# BeamBreak.net
KiCad netlist of a schematic drawn in EAGLE
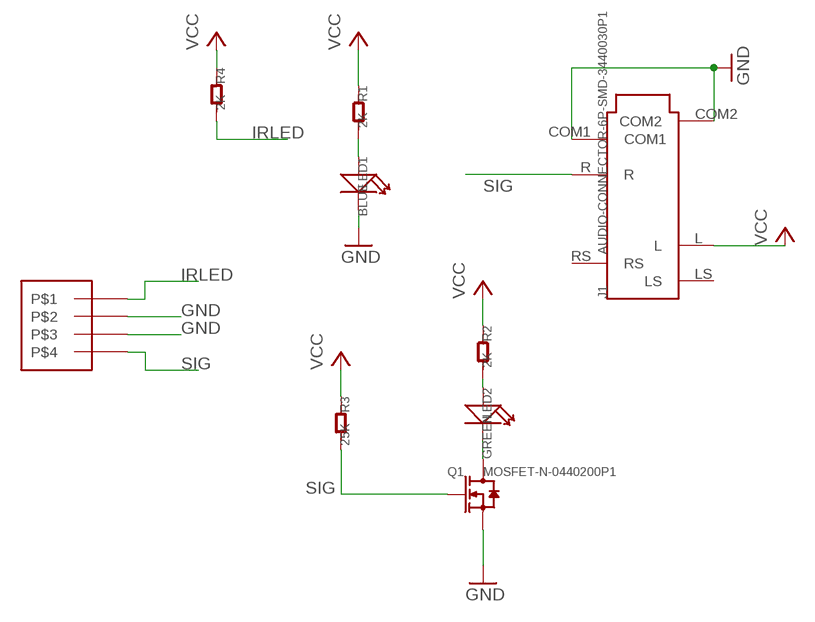
[diagram p0: schematic, sheet 1]

(export (version "E")
  (design (tool "Eeschema 10.0.6"))
  (components
    (comp (ref "J1")
      (value "AUDIO-CONNECTOR-6P-SMD-3440030P1")
      (footprint "eagle-import:6P-SMD-3.5")
      (libsource (lib "eagle-import") (part "AUDIO-CONNECTOR-6P-SMD-3440030P1"))
    )
    (comp (ref "LED1")
      (value "BLUE")
      (footprint "eagle-import:LED0603")
      (libsource (lib "eagle-import") (part "LED"))
    )
    (comp (ref "LED2")
      (value "GREEN")
      (footprint "eagle-import:LED0603")
      (libsource (lib "eagle-import") (part "LED"))
    )
    (comp (ref "Q1")
      (value "MOSFET-N-0440200P1")
      (footprint "eagle-import:SOT23")
      (libsource (lib "eagle-import") (part "MOSFET-N-0440200P1"))
    )
    (comp (ref "R1")
      (value "2K")
      (footprint "eagle-import:R0603")
      (libsource (lib "eagle-import") (part "R-0603"))
    )
    (comp (ref "R2")
      (value "2K")
      (footprint "eagle-import:R0603")
      (libsource (lib "eagle-import") (part "R-0603"))
    )
    (comp (ref "R3")
      (value "25K")
      (footprint "eagle-import:R0603")
      (libsource (lib "eagle-import") (part "R-0603"))
    )
    (comp (ref "R4")
      (value "2K")
      (footprint "eagle-import:R0603")
      (libsource (lib "eagle-import") (part "OPL_R-0603"))
    )
    (comp (ref "U$1")
      (value "HO4")
      (footprint "eagle-import:H04")
      (libsource (lib "eagle-import") (part "HO4"))
    )
  )
  (nets
    (net (code "1") (name "/IRLED") (class "Default")
      (node (ref "R4") (pin "2") (pinfunction "2_2") (pintype "bidirectional"))
      (node (ref "U$1") (pin "1") (pinfunction "P$1_1") (pintype "power_in"))
    )
    (net (code "2") (name "/SIG") (class "Default")
      (node (ref "J1") (pin "R") (pinfunction "R_R") (pintype "bidirectional"))
      (node (ref "Q1") (pin "1") (pinfunction "G_1") (pintype "passive"))
      (node (ref "R3") (pin "2") (pinfunction "2_2") (pintype "bidirectional"))
      (node (ref "U$1") (pin "4") (pinfunction "P$4_4") (pintype "power_in"))
    )
    (net (code "3") (name "GND") (class "Default")
      (node (ref "J1") (pin "COM1") (pinfunction "COM1_COM1") (pintype "bidirectional"))
      (node (ref "J1") (pin "COM2") (pinfunction "COM2_COM2") (pintype "bidirectional"))
      (node (ref "LED1") (pin "-") (pinfunction "-_-") (pintype "passive"))
      (node (ref "Q1") (pin "2") (pinfunction "S_2") (pintype "passive"))
      (node (ref "U$1") (pin "2") (pinfunction "P$2_2") (pintype "power_in"))
      (node (ref "U$1") (pin "3") (pinfunction "P$3_3") (pintype "power_in"))
    )
    (net (code "4") (name "Net-(LED1-Pad+)") (class "Default")
      (node (ref "LED1") (pin "+") (pinfunction "+_+") (pintype "passive"))
      (node (ref "R1") (pin "2") (pinfunction "2_2") (pintype "bidirectional"))
    )
    (net (code "5") (name "Net-(LED2-Pad+)") (class "Default")
      (node (ref "LED2") (pin "+") (pinfunction "+_+") (pintype "passive"))
      (node (ref "R2") (pin "2") (pinfunction "2_2") (pintype "bidirectional"))
    )
    (net (code "6") (name "Net-(Q1-D)") (class "Default")
      (node (ref "LED2") (pin "-") (pinfunction "-_-") (pintype "passive"))
      (node (ref "Q1") (pin "3") (pinfunction "D_3") (pintype "passive"))
    )
    (net (code "7") (name "VCC") (class "Default")
      (node (ref "J1") (pin "L") (pinfunction "L_L") (pintype "bidirectional"))
      (node (ref "R1") (pin "1") (pinfunction "1_1") (pintype "bidirectional"))
      (node (ref "R2") (pin "1") (pinfunction "1_1") (pintype "bidirectional"))
      (node (ref "R3") (pin "1") (pinfunction "1_1") (pintype "bidirectional"))
      (node (ref "R4") (pin "1") (pinfunction "1_1") (pintype "bidirectional"))
    )
    (net (code "8") (name "unconnected-(J1-PadLS)") (class "Default")
      (node (ref "J1") (pin "LS") (pinfunction "LS_LS") (pintype "bidirectional"))
    )
    (net (code "9") (name "unconnected-(J1-PadRS)") (class "Default")
      (node (ref "J1") (pin "RS") (pinfunction "RS_RS") (pintype "bidirectional"))
    )
  )
)
